# shift-register.net
KiCad netlist of a schematic drawn in EAGLE
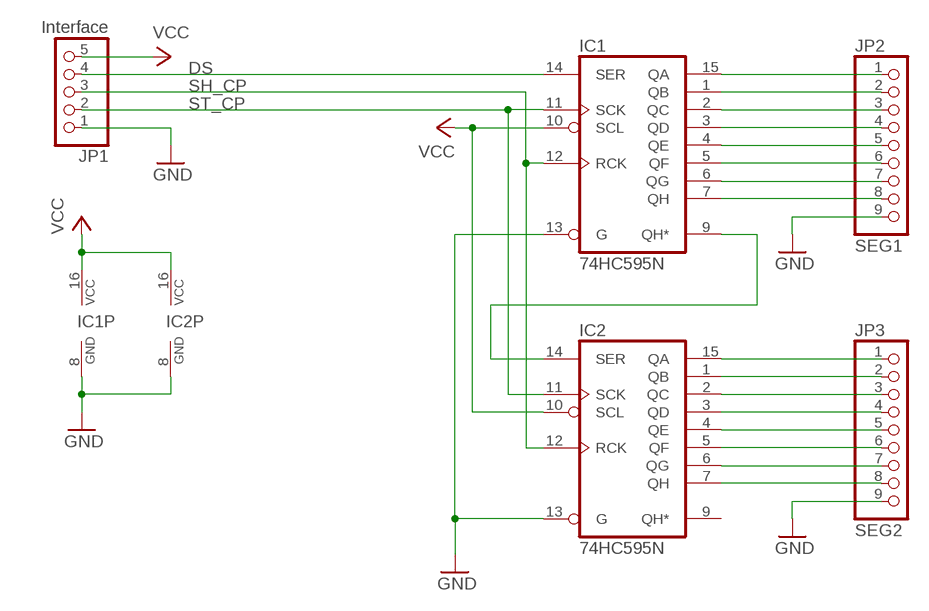
[diagram p0: schematic, sheet 1]

(export (version "E")
  (design (tool "Eeschema 10.0.6"))
  (components
    (comp (ref "IC1")
      (value "74HC595N")
      (footprint "eagle-import:DIL16")
      (libsource (lib "eagle-import") (part "74595NHC"))
    )
    (comp (ref "IC2")
      (value "74HC595N")
      (footprint "eagle-import:DIL16")
      (libsource (lib "eagle-import") (part "74595NHC"))
    )
    (comp (ref "JP1")
      (value "Interface")
      (footprint "eagle-import:1X05")
      (libsource (lib "eagle-import") (part "PINHD-1X5"))
    )
    (comp (ref "JP2")
      (value "SEG1")
      (footprint "eagle-import:1X09")
      (libsource (lib "eagle-import") (part "PINHD-1X9"))
    )
    (comp (ref "JP3")
      (value "SEG2")
      (footprint "eagle-import:1X09")
      (libsource (lib "eagle-import") (part "PINHD-1X9"))
    )
  )
  (nets
    (net (code "1") (name "/DS") (class "Default")
      (node (ref "IC1") (pin "14") (pinfunction "SER_14") (pintype "input"))
      (node (ref "JP1") (pin "4") (pinfunction "4_4") (pintype "passive"))
    )
    (net (code "2") (name "/SH_CP") (class "Default")
      (node (ref "IC1") (pin "12") (pinfunction "RCK_12") (pintype "input"))
      (node (ref "IC2") (pin "12") (pinfunction "RCK_12") (pintype "input"))
      (node (ref "JP1") (pin "3") (pinfunction "3_3") (pintype "passive"))
    )
    (net (code "3") (name "/ST_CP") (class "Default")
      (node (ref "IC1") (pin "11") (pinfunction "SCK_11") (pintype "input"))
      (node (ref "IC2") (pin "11") (pinfunction "SCK_11") (pintype "input"))
      (node (ref "JP1") (pin "2") (pinfunction "2_2") (pintype "passive"))
    )
    (net (code "4") (name "GND") (class "Default")
      (node (ref "IC1") (pin "13") (pinfunction "G_13") (pintype "input"))
      (node (ref "IC1") (pin "8") (pinfunction "GND_8") (pintype "power_in"))
      (node (ref "IC2") (pin "13") (pinfunction "G_13") (pintype "input"))
      (node (ref "IC2") (pin "8") (pinfunction "GND_8") (pintype "power_in"))
      (node (ref "JP1") (pin "1") (pinfunction "1_1") (pintype "passive"))
      (node (ref "JP2") (pin "9") (pinfunction "9_9") (pintype "passive"))
      (node (ref "JP3") (pin "9") (pinfunction "9_9") (pintype "passive"))
    )
    (net (code "5") (name "Net-(IC1A-QA)") (class "Default")
      (node (ref "IC1") (pin "15") (pinfunction "QA_15") (pintype "tri_state"))
      (node (ref "JP2") (pin "1") (pinfunction "1_1") (pintype "passive"))
    )
    (net (code "6") (name "Net-(IC1A-QB)") (class "Default")
      (node (ref "IC1") (pin "1") (pinfunction "QB_1") (pintype "tri_state"))
      (node (ref "JP2") (pin "2") (pinfunction "2_2") (pintype "passive"))
    )
    (net (code "7") (name "Net-(IC1A-QC)") (class "Default")
      (node (ref "IC1") (pin "2") (pinfunction "QC_2") (pintype "tri_state"))
      (node (ref "JP2") (pin "3") (pinfunction "3_3") (pintype "passive"))
    )
    (net (code "8") (name "Net-(IC1A-QD)") (class "Default")
      (node (ref "IC1") (pin "3") (pinfunction "QD_3") (pintype "tri_state"))
      (node (ref "JP2") (pin "4") (pinfunction "4_4") (pintype "passive"))
    )
    (net (code "9") (name "Net-(IC1A-QE)") (class "Default")
      (node (ref "IC1") (pin "4") (pinfunction "QE_4") (pintype "tri_state"))
      (node (ref "JP2") (pin "5") (pinfunction "5_5") (pintype "passive"))
    )
    (net (code "10") (name "Net-(IC1A-QF)") (class "Default")
      (node (ref "IC1") (pin "5") (pinfunction "QF_5") (pintype "tri_state"))
      (node (ref "JP2") (pin "6") (pinfunction "6_6") (pintype "passive"))
    )
    (net (code "11") (name "Net-(IC1A-QG)") (class "Default")
      (node (ref "IC1") (pin "6") (pinfunction "QG_6") (pintype "tri_state"))
      (node (ref "JP2") (pin "7") (pinfunction "7_7") (pintype "passive"))
    )
    (net (code "12") (name "Net-(IC1A-QH)") (class "Default")
      (node (ref "IC1") (pin "7") (pinfunction "QH_7") (pintype "tri_state"))
      (node (ref "JP2") (pin "8") (pinfunction "8_8") (pintype "passive"))
    )
    (net (code "13") (name "Net-(IC1A-QH*)") (class "Default")
      (node (ref "IC1") (pin "9") (pinfunction "QH*_9") (pintype "tri_state"))
      (node (ref "IC2") (pin "14") (pinfunction "SER_14") (pintype "input"))
    )
    (net (code "14") (name "Net-(IC2A-QA)") (class "Default")
      (node (ref "IC2") (pin "15") (pinfunction "QA_15") (pintype "tri_state"))
      (node (ref "JP3") (pin "1") (pinfunction "1_1") (pintype "passive"))
    )
    (net (code "15") (name "Net-(IC2A-QB)") (class "Default")
      (node (ref "IC2") (pin "1") (pinfunction "QB_1") (pintype "tri_state"))
      (node (ref "JP3") (pin "2") (pinfunction "2_2") (pintype "passive"))
    )
    (net (code "16") (name "Net-(IC2A-QC)") (class "Default")
      (node (ref "IC2") (pin "2") (pinfunction "QC_2") (pintype "tri_state"))
      (node (ref "JP3") (pin "3") (pinfunction "3_3") (pintype "passive"))
    )
    (net (code "17") (name "Net-(IC2A-QD)") (class "Default")
      (node (ref "IC2") (pin "3") (pinfunction "QD_3") (pintype "tri_state"))
      (node (ref "JP3") (pin "4") (pinfunction "4_4") (pintype "passive"))
    )
    (net (code "18") (name "Net-(IC2A-QE)") (class "Default")
      (node (ref "IC2") (pin "4") (pinfunction "QE_4") (pintype "tri_state"))
      (node (ref "JP3") (pin "5") (pinfunction "5_5") (pintype "passive"))
    )
    (net (code "19") (name "Net-(IC2A-QF)") (class "Default")
      (node (ref "IC2") (pin "5") (pinfunction "QF_5") (pintype "tri_state"))
      (node (ref "JP3") (pin "6") (pinfunction "6_6") (pintype "passive"))
    )
    (net (code "20") (name "Net-(IC2A-QG)") (class "Default")
      (node (ref "IC2") (pin "6") (pinfunction "QG_6") (pintype "tri_state"))
      (node (ref "JP3") (pin "7") (pinfunction "7_7") (pintype "passive"))
    )
    (net (code "21") (name "Net-(IC2A-QH)") (class "Default")
      (node (ref "IC2") (pin "7") (pinfunction "QH_7") (pintype "tri_state"))
      (node (ref "JP3") (pin "8") (pinfunction "8_8") (pintype "passive"))
    )
    (net (code "22") (name "VCC") (class "Default")
      (node (ref "IC1") (pin "10") (pinfunction "SCL_10") (pintype "input"))
      (node (ref "IC1") (pin "16") (pinfunction "VCC_16") (pintype "power_in"))
      (node (ref "IC2") (pin "10") (pinfunction "SCL_10") (pintype "input"))
      (node (ref "IC2") (pin "16") (pinfunction "VCC_16") (pintype "power_in"))
      (node (ref "JP1") (pin "5") (pinfunction "5_5") (pintype "passive"))
    )
    (net (code "23") (name "unconnected-(IC2A-QH*-Pad9)") (class "Default")
      (node (ref "IC2") (pin "9") (pinfunction "QH*_9") (pintype "tri_state"))
    )
  )
)
